# Lights_Project.net
KiCad netlist of a schematic drawn in EAGLE
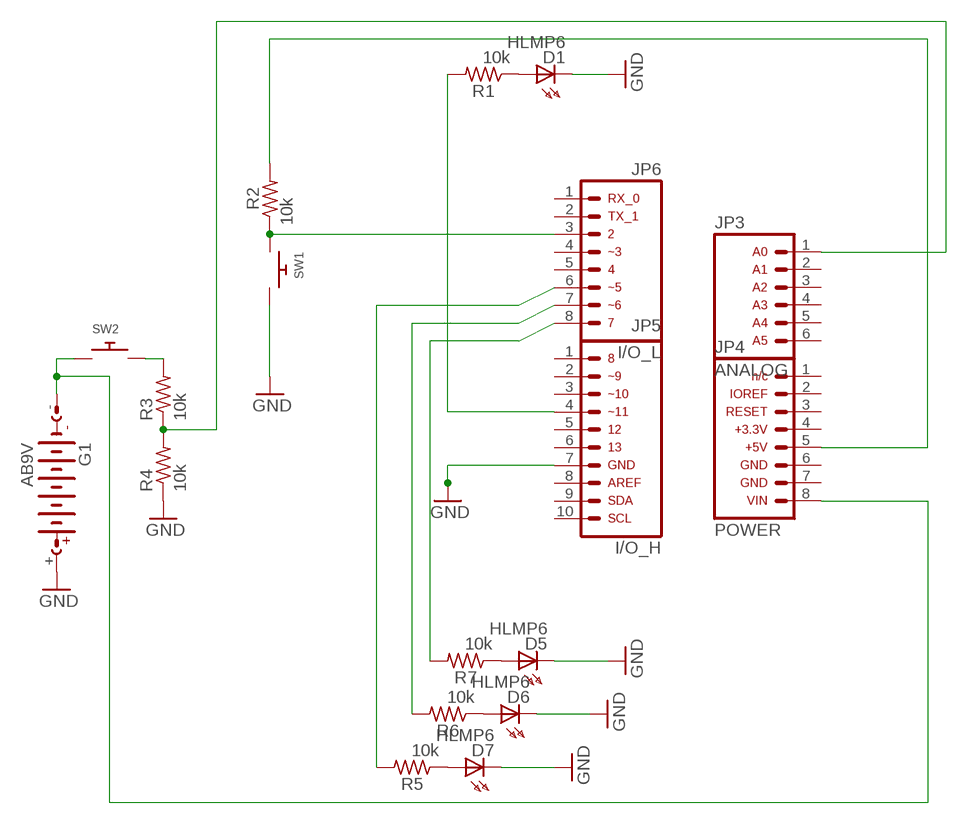
[diagram p0: schematic, sheet 1]

(export (version "E")
  (design (tool "Eeschema 10.0.6"))
  (components
    (comp (ref "D1")
      (value "HLMP6")
      (footprint "eagle-import:HLMP6")
      (fields (field (name "MF") "AGILENT TECHNOLOGIES") (field (name "MPN") "HLMP-6500"))
      (libsource (lib "eagle-import") (part "HLMP6"))
    )
    (comp (ref "D5")
      (value "HLMP6")
      (footprint "eagle-import:HLMP6")
      (fields (field (name "MF") "AGILENT TECHNOLOGIES") (field (name "MPN") "HLMP-6500"))
      (libsource (lib "eagle-import") (part "HLMP6"))
    )
    (comp (ref "D6")
      (value "HLMP6")
      (footprint "eagle-import:HLMP6")
      (fields (field (name "MF") "AGILENT TECHNOLOGIES") (field (name "MPN") "HLMP-6500"))
      (libsource (lib "eagle-import") (part "HLMP6"))
    )
    (comp (ref "D7")
      (value "HLMP6")
      (footprint "eagle-import:HLMP6")
      (fields (field (name "MF") "AGILENT TECHNOLOGIES") (field (name "MPN") "HLMP-6500"))
      (libsource (lib "eagle-import") (part "HLMP6"))
    )
    (comp (ref "G1")
      (value "AB9V")
      (footprint "eagle-import:AB9V")
      (libsource (lib "eagle-import") (part "AB9V"))
    )
    (comp (ref "JP3")
      (value "ARDUINO_CONN-ANALOGSIP")
      (footprint "eagle-import:CONN-1X06")
      (libsource (lib "eagle-import") (part "ARDUINO_CONN-ANALOGSIP"))
    )
    (comp (ref "JP4")
      (value "ARDUINO_CONN-POWERSIP")
      (footprint "eagle-import:CONN-1X08")
      (libsource (lib "eagle-import") (part "ARDUINO_CONN-POWERSIP"))
    )
    (comp (ref "JP5")
      (value "ARDUINO_CONN-IO_HSIP")
      (footprint "eagle-import:CONN-1X10")
      (libsource (lib "eagle-import") (part "ARDUINO_CONN-IO_HSIP"))
    )
    (comp (ref "JP6")
      (value "ARDUINO_CONN-IO_LSIP")
      (footprint "eagle-import:CONN-1X08")
      (libsource (lib "eagle-import") (part "ARDUINO_CONN-IO_LSIP"))
    )
    (comp (ref "R1")
      (value "10k")
      (footprint "eagle-import:R0805")
      (libsource (lib "eagle-import") (part "R-US_R0805"))
    )
    (comp (ref "R2")
      (value "10k")
      (footprint "eagle-import:R0805")
      (libsource (lib "eagle-import") (part "R-US_R0805"))
    )
    (comp (ref "R3")
      (value "10k")
      (footprint "eagle-import:R0805")
      (libsource (lib "eagle-import") (part "R-US_R0805"))
    )
    (comp (ref "R4")
      (value "10k")
      (footprint "eagle-import:R0805")
      (libsource (lib "eagle-import") (part "R-US_R0805"))
    )
    (comp (ref "R5")
      (value "10k")
      (footprint "eagle-import:R0805")
      (libsource (lib "eagle-import") (part "R-US_R0805"))
    )
    (comp (ref "R6")
      (value "10k")
      (footprint "eagle-import:R0805")
      (libsource (lib "eagle-import") (part "R-US_R0805"))
    )
    (comp (ref "R7")
      (value "10k")
      (footprint "eagle-import:R0805")
      (libsource (lib "eagle-import") (part "R-US_R0805"))
    )
    (comp (ref "SW1")
      (value "SWITCH_PUSHBUTTONSOFTTOUCHSMD_SJ")
      (footprint "eagle-import:PUSHBUTTON_SMD_SJ")
      (libsource (lib "eagle-import") (part "SWITCH_PUSHBUTTONSOFTTOUCHSMD_SJ"))
    )
    (comp (ref "SW2")
      (value "SWITCH_PUSHBUTTONSOFTTOUCHSMD_SJ")
      (footprint "eagle-import:PUSHBUTTON_SMD_SJ")
      (libsource (lib "eagle-import") (part "SWITCH_PUSHBUTTONSOFTTOUCHSMD_SJ"))
    )
  )
  (nets
    (net (code "1") (name "GND") (class "Default")
      (node (ref "D1") (pin "K") (pinfunction "K_K") (pintype "passive"))
      (node (ref "D5") (pin "K") (pinfunction "K_K") (pintype "passive"))
      (node (ref "D6") (pin "K") (pinfunction "K_K") (pintype "passive"))
      (node (ref "D7") (pin "K") (pinfunction "K_K") (pintype "passive"))
      (node (ref "G1") (pin "+") (pinfunction "+_+") (pintype "passive"))
      (node (ref "JP5") (pin "7") (pinfunction "7_7") (pintype "passive"))
      (node (ref "R4") (pin "1") (pinfunction "1_1") (pintype "passive"))
      (node (ref "SW1") (pin "P$2") (pinfunction "P$2_P$2") (pintype "passive"))
    )
    (net (code "2") (name "Net-(D1-PadA)") (class "Default")
      (node (ref "D1") (pin "A") (pinfunction "A_A") (pintype "passive"))
      (node (ref "R1") (pin "1") (pinfunction "1_1") (pintype "passive"))
    )
    (net (code "3") (name "Net-(D5-PadA)") (class "Default")
      (node (ref "D5") (pin "A") (pinfunction "A_A") (pintype "passive"))
      (node (ref "R7") (pin "1") (pinfunction "1_1") (pintype "passive"))
    )
    (net (code "4") (name "Net-(D6-PadA)") (class "Default")
      (node (ref "D6") (pin "A") (pinfunction "A_A") (pintype "passive"))
      (node (ref "R6") (pin "1") (pinfunction "1_1") (pintype "passive"))
    )
    (net (code "5") (name "Net-(D7-PadA)") (class "Default")
      (node (ref "D7") (pin "A") (pinfunction "A_A") (pintype "passive"))
      (node (ref "R5") (pin "1") (pinfunction "1_1") (pintype "passive"))
    )
    (net (code "6") (name "Net-(G1-Pad-)") (class "Default")
      (node (ref "G1") (pin "-") (pinfunction "-_-") (pintype "passive"))
      (node (ref "JP4") (pin "8") (pinfunction "8_8") (pintype "passive"))
      (node (ref "SW2") (pin "P$1") (pinfunction "P$1_P$1") (pintype "passive"))
    )
    (net (code "7") (name "Net-(JP3-Pad1)") (class "Default")
      (node (ref "JP3") (pin "1") (pinfunction "1_1") (pintype "passive"))
      (node (ref "R3") (pin "1") (pinfunction "1_1") (pintype "passive"))
      (node (ref "R4") (pin "2") (pinfunction "2_2") (pintype "passive"))
    )
    (net (code "8") (name "Net-(JP4-Pad5)") (class "Default")
      (node (ref "JP4") (pin "5") (pinfunction "5_5") (pintype "passive"))
      (node (ref "R2") (pin "2") (pinfunction "2_2") (pintype "passive"))
    )
    (net (code "9") (name "Net-(JP5-Pad4)") (class "Default")
      (node (ref "JP5") (pin "4") (pinfunction "4_4") (pintype "passive"))
      (node (ref "R1") (pin "2") (pinfunction "2_2") (pintype "passive"))
    )
    (net (code "10") (name "Net-(JP6-Pad3)") (class "Default")
      (node (ref "JP6") (pin "3") (pinfunction "3_3") (pintype "passive"))
      (node (ref "R2") (pin "1") (pinfunction "1_1") (pintype "passive"))
      (node (ref "SW1") (pin "P$1") (pinfunction "P$1_P$1") (pintype "passive"))
    )
    (net (code "11") (name "Net-(JP6-Pad6)") (class "Default")
      (node (ref "JP6") (pin "6") (pinfunction "6_6") (pintype "passive"))
      (node (ref "R5") (pin "2") (pinfunction "2_2") (pintype "passive"))
    )
    (net (code "12") (name "Net-(JP6-Pad7)") (class "Default")
      (node (ref "JP6") (pin "7") (pinfunction "7_7") (pintype "passive"))
      (node (ref "R6") (pin "2") (pinfunction "2_2") (pintype "passive"))
    )
    (net (code "13") (name "Net-(JP6-Pad8)") (class "Default")
      (node (ref "JP6") (pin "8") (pinfunction "8_8") (pintype "passive"))
      (node (ref "R7") (pin "2") (pinfunction "2_2") (pintype "passive"))
    )
    (net (code "14") (name "Net-(R3-Pad2)") (class "Default")
      (node (ref "R3") (pin "2") (pinfunction "2_2") (pintype "passive"))
      (node (ref "SW2") (pin "P$2") (pinfunction "P$2_P$2") (pintype "passive"))
    )
    (net (code "15") (name "unconnected-(JP3-Pad2)") (class "Default")
      (node (ref "JP3") (pin "2") (pinfunction "2_2") (pintype "passive"))
    )
    (net (code "16") (name "unconnected-(JP3-Pad3)") (class "Default")
      (node (ref "JP3") (pin "3") (pinfunction "3_3") (pintype "passive"))
    )
    (net (code "17") (name "unconnected-(JP3-Pad4)") (class "Default")
      (node (ref "JP3") (pin "4") (pinfunction "4_4") (pintype "passive"))
    )
    (net (code "18") (name "unconnected-(JP3-Pad5)") (class "Default")
      (node (ref "JP3") (pin "5") (pinfunction "5_5") (pintype "passive"))
    )
    (net (code "19") (name "unconnected-(JP3-Pad6)") (class "Default")
      (node (ref "JP3") (pin "6") (pinfunction "6_6") (pintype "passive"))
    )
    (net (code "20") (name "unconnected-(JP4-Pad1)") (class "Default")
      (node (ref "JP4") (pin "1") (pinfunction "1_1") (pintype "passive"))
    )
    (net (code "21") (name "unconnected-(JP4-Pad2)") (class "Default")
      (node (ref "JP4") (pin "2") (pinfunction "2_2") (pintype "passive"))
    )
    (net (code "22") (name "unconnected-(JP4-Pad3)") (class "Default")
      (node (ref "JP4") (pin "3") (pinfunction "3_3") (pintype "passive"))
    )
    (net (code "23") (name "unconnected-(JP4-Pad4)") (class "Default")
      (node (ref "JP4") (pin "4") (pinfunction "4_4") (pintype "passive"))
    )
    (net (code "24") (name "unconnected-(JP4-Pad6)") (class "Default")
      (node (ref "JP4") (pin "6") (pinfunction "6_6") (pintype "passive"))
    )
    (net (code "25") (name "unconnected-(JP4-Pad7)") (class "Default")
      (node (ref "JP4") (pin "7") (pinfunction "7_7") (pintype "passive"))
    )
    (net (code "26") (name "unconnected-(JP5-Pad1)") (class "Default")
      (node (ref "JP5") (pin "1") (pinfunction "1_1") (pintype "passive"))
    )
    (net (code "27") (name "unconnected-(JP5-Pad2)") (class "Default")
      (node (ref "JP5") (pin "2") (pinfunction "2_2") (pintype "passive"))
    )
    (net (code "28") (name "unconnected-(JP5-Pad3)") (class "Default")
      (node (ref "JP5") (pin "3") (pinfunction "3_3") (pintype "passive"))
    )
    (net (code "29") (name "unconnected-(JP5-Pad5)") (class "Default")
      (node (ref "JP5") (pin "5") (pinfunction "5_5") (pintype "passive"))
    )
    (net (code "30") (name "unconnected-(JP5-Pad6)") (class "Default")
      (node (ref "JP5") (pin "6") (pinfunction "6_6") (pintype "passive"))
    )
    (net (code "31") (name "unconnected-(JP5-Pad8)") (class "Default")
      (node (ref "JP5") (pin "8") (pinfunction "8_8") (pintype "passive"))
    )
    (net (code "32") (name "unconnected-(JP5-Pad9)") (class "Default")
      (node (ref "JP5") (pin "9") (pinfunction "9_9") (pintype "passive"))
    )
    (net (code "33") (name "unconnected-(JP5-Pad10)") (class "Default")
      (node (ref "JP5") (pin "10") (pinfunction "10_10") (pintype "passive"))
    )
    (net (code "34") (name "unconnected-(JP6-Pad1)") (class "Default")
      (node (ref "JP6") (pin "1") (pinfunction "1_1") (pintype "passive"))
    )
    (net (code "35") (name "unconnected-(JP6-Pad2)") (class "Default")
      (node (ref "JP6") (pin "2") (pinfunction "2_2") (pintype "passive"))
    )
    (net (code "36") (name "unconnected-(JP6-Pad4)") (class "Default")
      (node (ref "JP6") (pin "4") (pinfunction "4_4") (pintype "passive"))
    )
    (net (code "37") (name "unconnected-(JP6-Pad5)") (class "Default")
      (node (ref "JP6") (pin "5") (pinfunction "5_5") (pintype "passive"))
    )
  )
)
